# 16-Channel_PWM_Driver_PCA9685.net
KiCad netlist of a schematic drawn in EAGLE
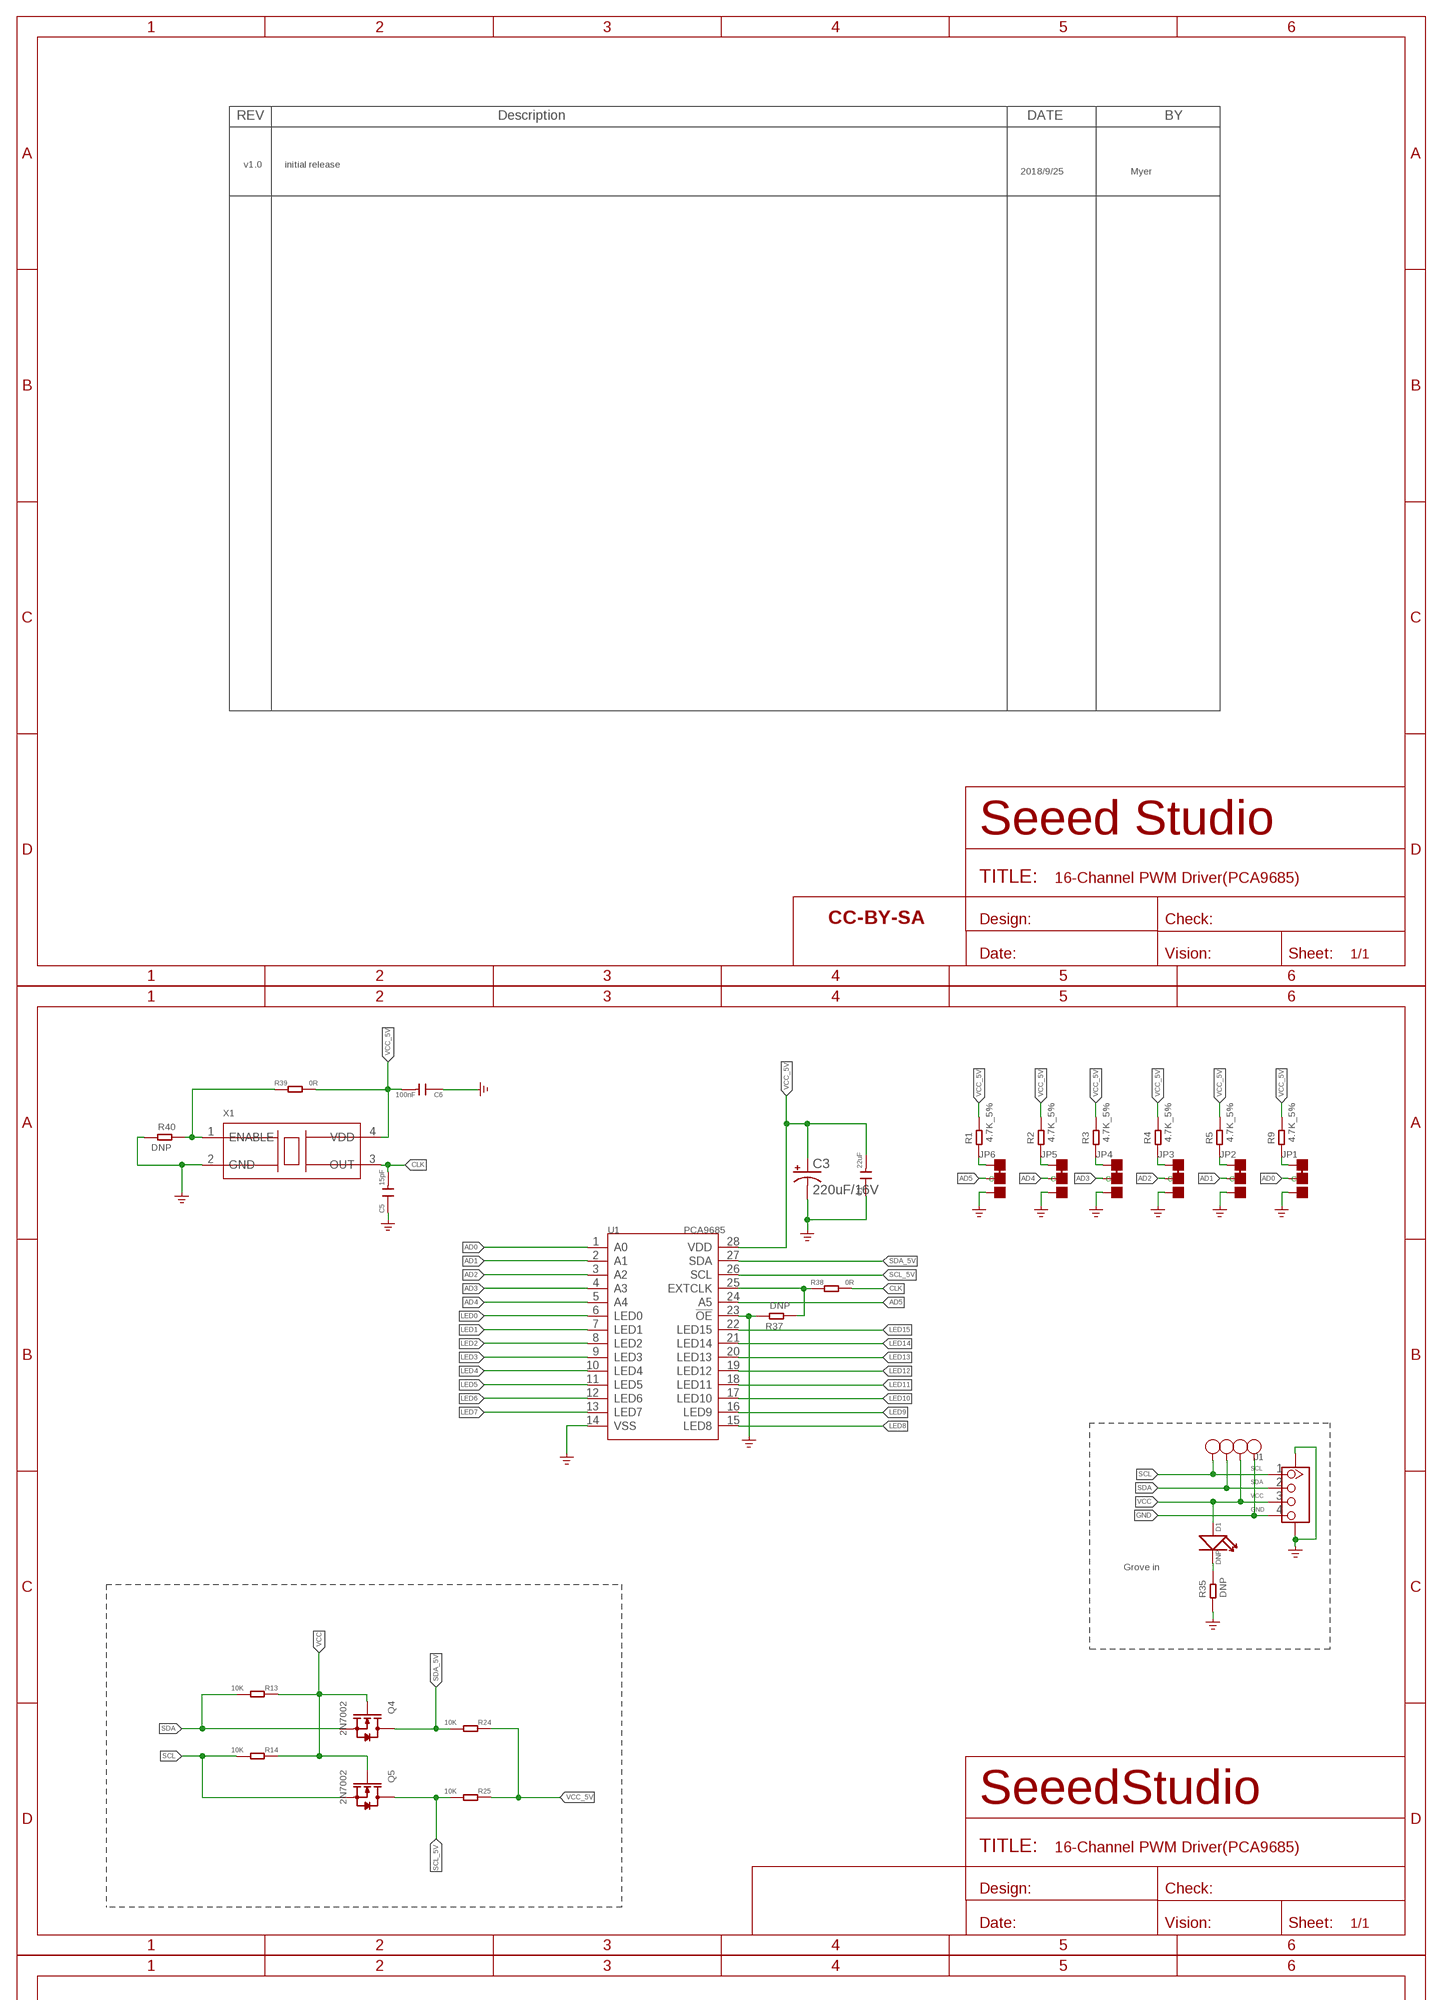
[diagram p0: schematic, sheet 1, part 1 of 2]
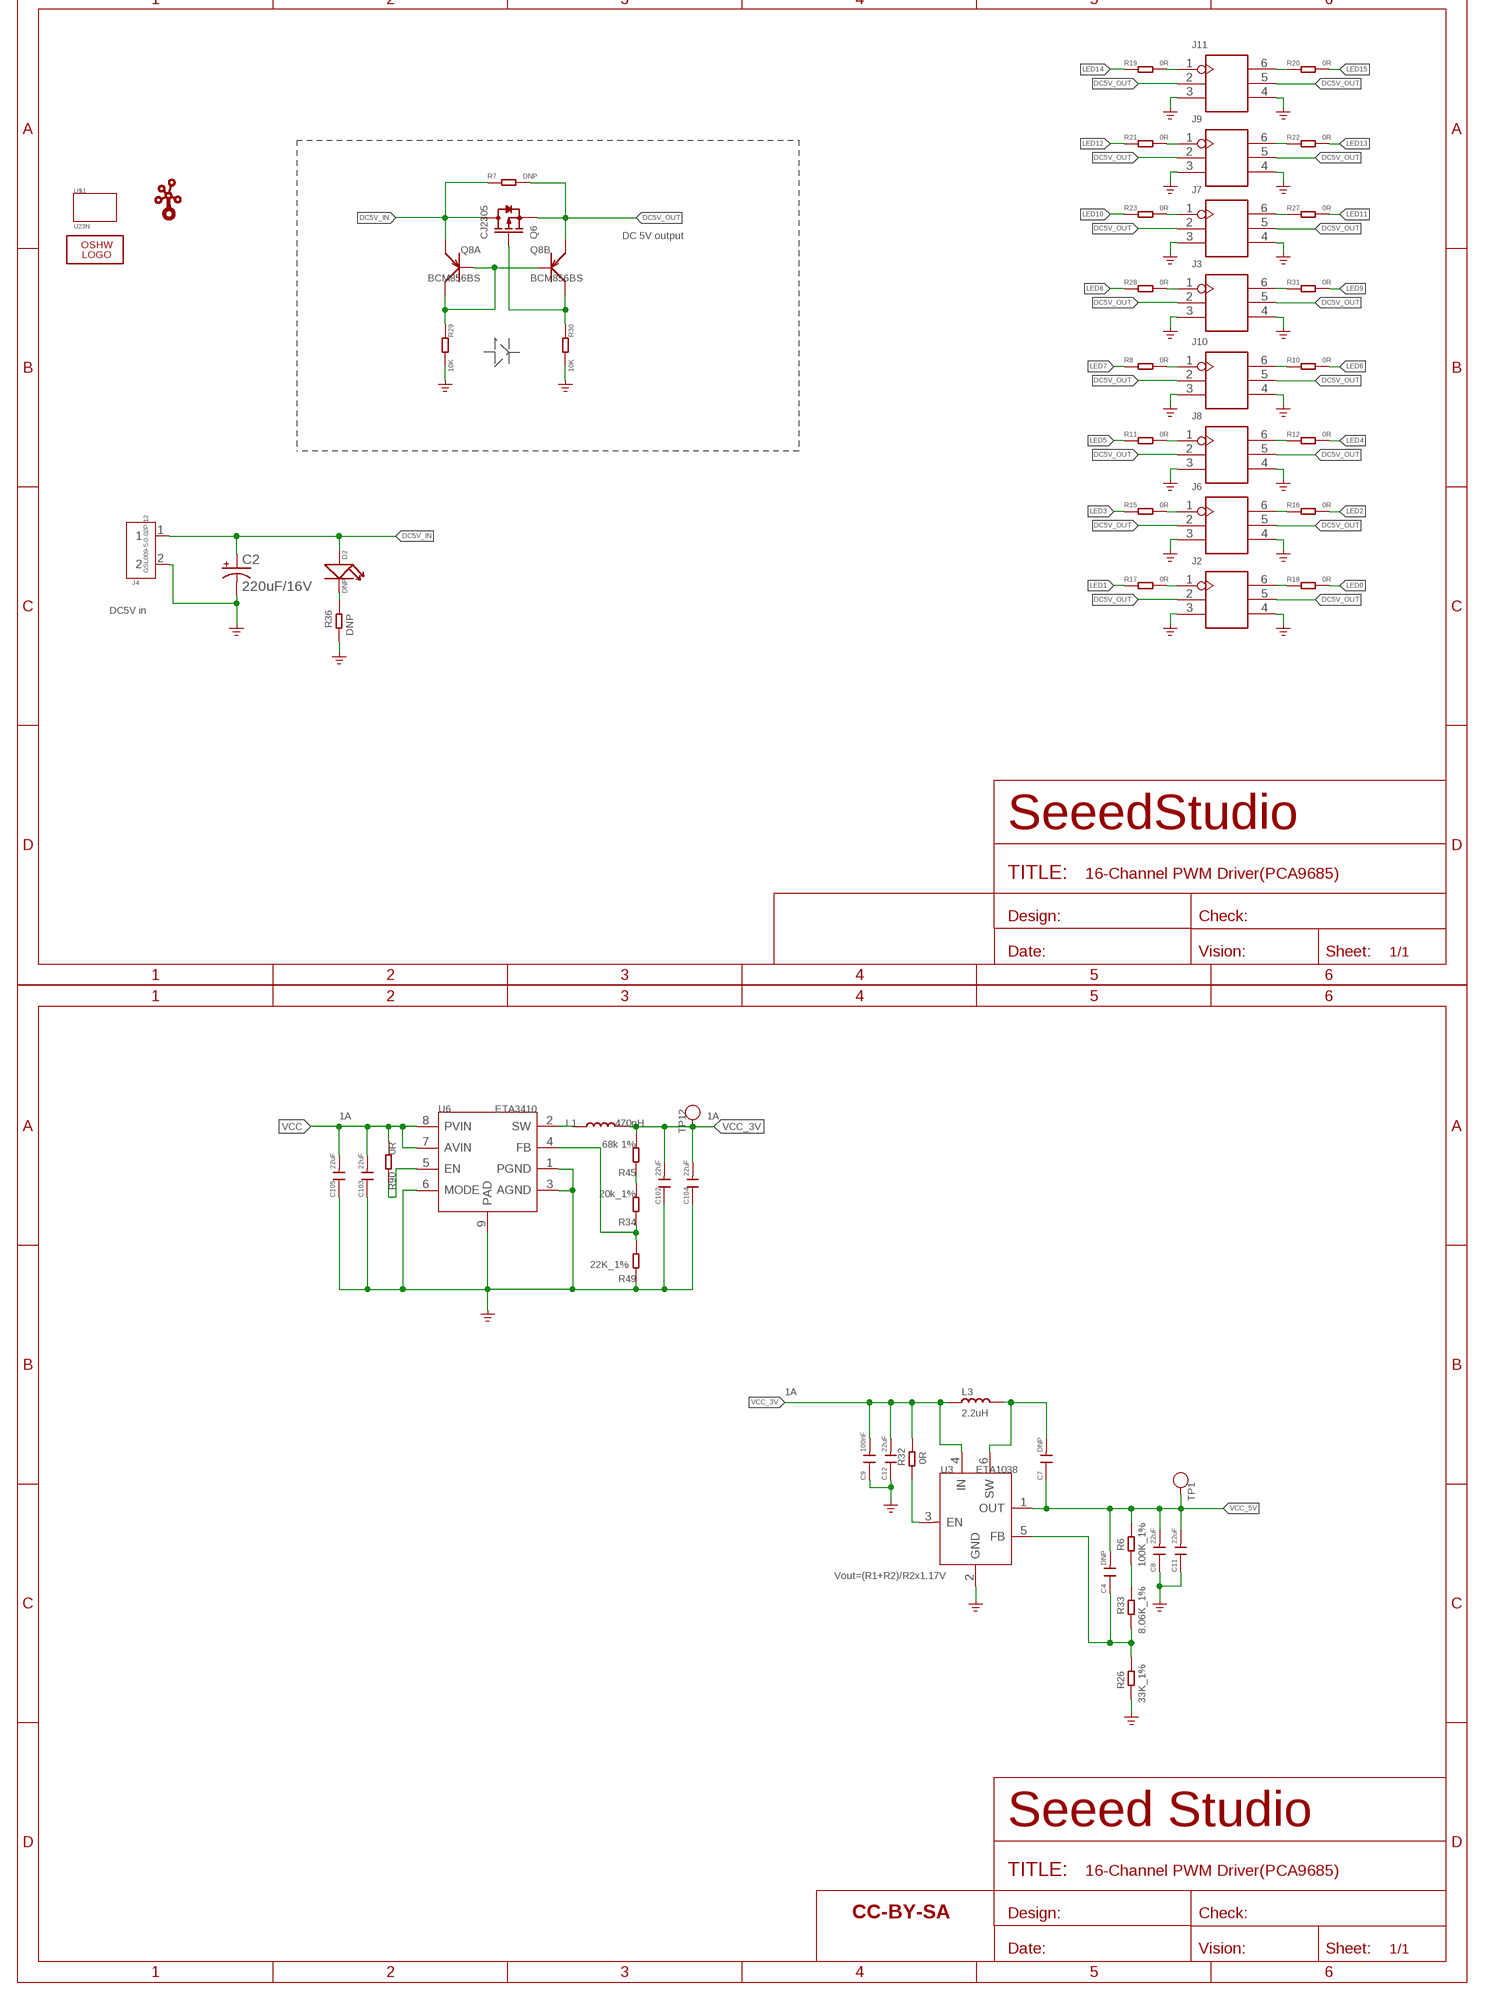
[diagram p1: schematic, sheet 1, part 2 of 2]

(export (version "E")
  (design (tool "Eeschema 10.0.6"))
  (components
    (comp (ref "C1")
      (value "22uF")
      (footprint "eagle-import:C0805")
      (libsource (lib "eagle-import") (part "C-0805"))
    )
    (comp (ref "C2")
      (value "220uF/16V")
      (footprint "eagle-import:PANASONIC_D")
      (libsource (lib "eagle-import") (part "CPOL-USD"))
    )
    (comp (ref "C3")
      (value "220uF/16V")
      (footprint "eagle-import:PANASONIC_D")
      (libsource (lib "eagle-import") (part "CPOL-USD"))
    )
    (comp (ref "C4")
      (value "DNP")
      (footprint "eagle-import:C0603")
      (libsource (lib "eagle-import") (part "C-0603"))
    )
    (comp (ref "C5")
      (value "15pF")
      (footprint "eagle-import:C0603")
      (libsource (lib "eagle-import") (part "C-0603"))
    )
    (comp (ref "C6")
      (value "100nF")
      (footprint "eagle-import:C0603")
      (libsource (lib "eagle-import") (part "C-0603"))
    )
    (comp (ref "C7")
      (value "DNP")
      (footprint "eagle-import:C0603")
      (libsource (lib "eagle-import") (part "C-0603"))
    )
    (comp (ref "C8")
      (value "22uF")
      (footprint "eagle-import:C0603")
      (libsource (lib "eagle-import") (part "C-0603"))
    )
    (comp (ref "C9")
      (value "100nF")
      (footprint "eagle-import:C0603")
      (libsource (lib "eagle-import") (part "C-0603"))
    )
    (comp (ref "C11")
      (value "22uF")
      (footprint "eagle-import:C0603")
      (libsource (lib "eagle-import") (part "C-0603"))
    )
    (comp (ref "C12")
      (value "22uF")
      (footprint "eagle-import:C0603")
      (libsource (lib "eagle-import") (part "C-0603"))
    )
    (comp (ref "C102")
      (value "22uF")
      (footprint "eagle-import:C0603")
      (libsource (lib "eagle-import") (part "C-0603"))
    )
    (comp (ref "C103")
      (value "22uF")
      (footprint "eagle-import:C0603")
      (libsource (lib "eagle-import") (part "C-0603"))
    )
    (comp (ref "C104")
      (value "22uF")
      (footprint "eagle-import:C0603")
      (libsource (lib "eagle-import") (part "C-0603"))
    )
    (comp (ref "C105")
      (value "22uF")
      (footprint "eagle-import:C0603")
      (libsource (lib "eagle-import") (part "C-0603"))
    )
    (comp (ref "D1")
      (value "DNP")
      (footprint "eagle-import:LED-0603")
      (libsource (lib "eagle-import") (part "LED'0603'"))
    )
    (comp (ref "D2")
      (value "DNP")
      (footprint "eagle-import:LED-0603")
      (libsource (lib "eagle-import") (part "LED'0603'"))
    )
    (comp (ref "FR1")
      (value "SEEEDSTUDIO-OPEN-SCH-FRAME")
      (footprint "eagle-import:SEEEDSTUDIO-PCB-FRAME")
      (libsource (lib "eagle-import") (part "SEEEDSTUDIO-OPEN-SCH-FRAME"))
    )
    (comp (ref "FR2")
      (value "SEEEDSTUDIO-OPEN-SCH-FRAME")
      (footprint "eagle-import:SEEEDSTUDIO-PCB-FRAME")
      (libsource (lib "eagle-import") (part "SEEEDSTUDIO-OPEN-SCH-FRAME"))
    )
    (comp (ref "GND1")
      (value "TEST-POINT'4545'")
      (footprint "eagle-import:TP-D45MIL")
      (fields (field (name "PARTNO") "DNP"))
      (libsource (lib "eagle-import") (part "TEST-POINT'4545'"))
    )
    (comp (ref "J1")
      (value "GROVE-CONNECTOR-SMD'90D'")
      (footprint "eagle-import:HW4-SMD-2.0-90D")
      (libsource (lib "eagle-import") (part "GROVE-CONNECTOR-SMD'90D'"))
    )
    (comp (ref "J2")
      (value "HEADER-2X3P-2.54")
      (footprint "eagle-import:H2X3-2.54")
      (libsource (lib "eagle-import") (part "HEADER-2X3P-2.54"))
    )
    (comp (ref "J3")
      (value "HEADER-2X3P-2.54")
      (footprint "eagle-import:H2X3-2.54")
      (libsource (lib "eagle-import") (part "HEADER-2X3P-2.54"))
    )
    (comp (ref "J4")
      (value "GSL009-5.0-02P-12")
      (footprint "eagle-import:2P-5.0-10.6X10X14.8H")
      (libsource (lib "eagle-import") (part "SCREW-TERMINAL-2P'5.0-10.6X10X14.8H'"))
    )
    (comp (ref "J6")
      (value "HEADER-2X3P-2.54")
      (footprint "eagle-import:H2X3-2.54")
      (libsource (lib "eagle-import") (part "HEADER-2X3P-2.54"))
    )
    (comp (ref "J7")
      (value "HEADER-2X3P-2.54")
      (footprint "eagle-import:H2X3-2.54")
      (libsource (lib "eagle-import") (part "HEADER-2X3P-2.54"))
    )
    (comp (ref "J8")
      (value "HEADER-2X3P-2.54")
      (footprint "eagle-import:H2X3-2.54")
      (libsource (lib "eagle-import") (part "HEADER-2X3P-2.54"))
    )
    (comp (ref "J9")
      (value "HEADER-2X3P-2.54")
      (footprint "eagle-import:H2X3-2.54")
      (libsource (lib "eagle-import") (part "HEADER-2X3P-2.54"))
    )
    (comp (ref "J10")
      (value "HEADER-2X3P-2.54")
      (footprint "eagle-import:H2X3-2.54")
      (libsource (lib "eagle-import") (part "HEADER-2X3P-2.54"))
    )
    (comp (ref "J11")
      (value "HEADER-2X3P-2.54")
      (footprint "eagle-import:H2X3-2.54")
      (libsource (lib "eagle-import") (part "HEADER-2X3P-2.54"))
    )
    (comp (ref "JP1")
      (value "JP-3P-SHORT")
      (footprint "eagle-import:3P-SMD-SHORT")
      (libsource (lib "eagle-import") (part "JP-3P-SHORT"))
    )
    (comp (ref "JP2")
      (value "JP-3P-SHORT")
      (footprint "eagle-import:3P-SMD-SHORT")
      (libsource (lib "eagle-import") (part "JP-3P-SHORT"))
    )
    (comp (ref "JP3")
      (value "JP-3P-SHORT")
      (footprint "eagle-import:3P-SMD-SHORT")
      (libsource (lib "eagle-import") (part "JP-3P-SHORT"))
    )
    (comp (ref "JP4")
      (value "JP-3P-SHORT")
      (footprint "eagle-import:3P-SMD-SHORT")
      (libsource (lib "eagle-import") (part "JP-3P-SHORT"))
    )
    (comp (ref "JP5")
      (value "JP-3P-SHORT")
      (footprint "eagle-import:3P-SMD-SHORT")
      (libsource (lib "eagle-import") (part "JP-3P-SHORT"))
    )
    (comp (ref "JP6")
      (value "JP-3P-SHORT")
      (footprint "eagle-import:3P-SMD-SHORT")
      (libsource (lib "eagle-import") (part "JP-3P-SHORT"))
    )
    (comp (ref "L1")
      (value "470nH")
      (footprint "eagle-import:L201610")
      (libsource (lib "eagle-import") (part "L-MPM201610SR33_T"))
    )
    (comp (ref "L3")
      (value "2.2uH")
      (footprint "eagle-import:L0806")
      (libsource (lib "eagle-import") (part "INDUCTOR/FERRITE-BEAD'0806'"))
    )
    (comp (ref "LOGO2")
      (value "LOGO-OSHW-FILLX0200-NT")
      (footprint "eagle-import:OSHW_FILLX200_NOTEXT")
      (fields (field (name "PARTNO") "DNP"))
      (libsource (lib "eagle-import") (part "LOGO-OSHW-FILLX0200-NT"))
    )
    (comp (ref "Q4")
      (value "2N7002")
      (footprint "eagle-import:SOT-323")
      (libsource (lib "eagle-import") (part "MOSFET-N+'SI1304BDL'"))
    )
    (comp (ref "Q5")
      (value "2N7002")
      (footprint "eagle-import:SOT-323")
      (libsource (lib "eagle-import") (part "MOSFET-N+'SI1304BDL'"))
    )
    (comp (ref "Q6")
      (value "CJ2305")
      (footprint "eagle-import:SOT-23")
      (libsource (lib "eagle-import") (part "MOSFET-P'SI2323CDS/SI2305DS{lt}BR{gt}'"))
    )
    (comp (ref "Q8")
      (value "BCM856BS")
      (footprint "eagle-import:SOT-363")
      (libsource (lib "eagle-import") (part "TRANSISTOR-DUAL-PNP"))
    )
    (comp (ref "R1")
      (value "4.7K_5%")
      (footprint "eagle-import:R0603")
      (libsource (lib "eagle-import") (part "R-0603"))
    )
    (comp (ref "R2")
      (value "4.7K_5%")
      (footprint "eagle-import:R0603")
      (libsource (lib "eagle-import") (part "R-0603"))
    )
    (comp (ref "R3")
      (value "4.7K_5%")
      (footprint "eagle-import:R0603")
      (libsource (lib "eagle-import") (part "R-0603"))
    )
    (comp (ref "R4")
      (value "4.7K_5%")
      (footprint "eagle-import:R0603")
      (libsource (lib "eagle-import") (part "R-0603"))
    )
    (comp (ref "R5")
      (value "4.7K_5%")
      (footprint "eagle-import:R0603")
      (libsource (lib "eagle-import") (part "R-0603"))
    )
    (comp (ref "R6")
      (value "100K_1%")
      (footprint "eagle-import:R0603")
      (libsource (lib "eagle-import") (part "R-0603"))
    )
    (comp (ref "R7")
      (value "DNP")
      (footprint "eagle-import:R0805")
      (libsource (lib "eagle-import") (part "R-0805"))
    )
    (comp (ref "R8")
      (value "0R")
      (footprint "eagle-import:R0603")
      (libsource (lib "eagle-import") (part "R-0603"))
    )
    (comp (ref "R9")
      (value "4.7K_5%")
      (footprint "eagle-import:R0603")
      (libsource (lib "eagle-import") (part "R-0603"))
    )
    (comp (ref "R10")
      (value "0R")
      (footprint "eagle-import:R0603")
      (libsource (lib "eagle-import") (part "R-0603"))
    )
    (comp (ref "R11")
      (value "0R")
      (footprint "eagle-import:R0603")
      (libsource (lib "eagle-import") (part "R-0603"))
    )
    (comp (ref "R12")
      (value "0R")
      (footprint "eagle-import:R0603")
      (libsource (lib "eagle-import") (part "R-0603"))
    )
    (comp (ref "R13")
      (value "10K")
      (footprint "eagle-import:R0603")
      (libsource (lib "eagle-import") (part "R-0603"))
    )
    (comp (ref "R14")
      (value "10K")
      (footprint "eagle-import:R0603")
      (libsource (lib "eagle-import") (part "R-0603"))
    )
    (comp (ref "R15")
      (value "0R")
      (footprint "eagle-import:R0603")
      (libsource (lib "eagle-import") (part "R-0603"))
    )
    (comp (ref "R16")
      (value "0R")
      (footprint "eagle-import:R0603")
      (libsource (lib "eagle-import") (part "R-0603"))
    )
    (comp (ref "R17")
      (value "0R")
      (footprint "eagle-import:R0603")
      (libsource (lib "eagle-import") (part "R-0603"))
    )
    (comp (ref "R18")
      (value "0R")
      (footprint "eagle-import:R0603")
      (libsource (lib "eagle-import") (part "R-0603"))
    )
    (comp (ref "R19")
      (value "0R")
      (footprint "eagle-import:R0603")
      (libsource (lib "eagle-import") (part "R-0603"))
    )
    (comp (ref "R20")
      (value "0R")
      (footprint "eagle-import:R0603")
      (libsource (lib "eagle-import") (part "R-0603"))
    )
    (comp (ref "R21")
      (value "0R")
      (footprint "eagle-import:R0603")
      (libsource (lib "eagle-import") (part "R-0603"))
    )
    (comp (ref "R22")
      (value "0R")
      (footprint "eagle-import:R0603")
      (libsource (lib "eagle-import") (part "R-0603"))
    )
    (comp (ref "R23")
      (value "0R")
      (footprint "eagle-import:R0603")
      (libsource (lib "eagle-import") (part "R-0603"))
    )
    (comp (ref "R24")
      (value "10K")
      (footprint "eagle-import:R0603")
      (libsource (lib "eagle-import") (part "R-0603"))
    )
    (comp (ref "R25")
      (value "10K")
      (footprint "eagle-import:R0603")
      (libsource (lib "eagle-import") (part "R-0603"))
    )
    (comp (ref "R26")
      (value "33K_1%")
      (footprint "eagle-import:R0603")
      (libsource (lib "eagle-import") (part "R-0603"))
    )
    (comp (ref "R27")
      (value "0R")
      (footprint "eagle-import:R0603")
      (libsource (lib "eagle-import") (part "R-0603"))
    )
    (comp (ref "R28")
      (value "0R")
      (footprint "eagle-import:R0603")
      (libsource (lib "eagle-import") (part "R-0603"))
    )
    (comp (ref "R29")
      (value "10K")
      (footprint "eagle-import:R0603")
      (libsource (lib "eagle-import") (part "R-0603"))
    )
    (comp (ref "R30")
      (value "10K")
      (footprint "eagle-import:R0603")
      (libsource (lib "eagle-import") (part "R-0603"))
    )
    (comp (ref "R31")
      (value "0R")
      (footprint "eagle-import:R0603")
      (libsource (lib "eagle-import") (part "R-0603"))
    )
    (comp (ref "R32")
      (value "0R")
      (footprint "eagle-import:R0603")
      (libsource (lib "eagle-import") (part "R-0603"))
    )
    (comp (ref "R33")
      (value "8.06K_1%")
      (footprint "eagle-import:R0603")
      (libsource (lib "eagle-import") (part "R-0603"))
    )
    (comp (ref "R34")
      (value "20k_1%")
      (footprint "eagle-import:R0603")
      (libsource (lib "eagle-import") (part "R-0603"))
    )
    (comp (ref "R35")
      (value "DNP")
      (footprint "eagle-import:R0603")
      (libsource (lib "eagle-import") (part "R-0603"))
    )
    (comp (ref "R36")
      (value "DNP")
      (footprint "eagle-import:R0603")
      (libsource (lib "eagle-import") (part "R-0603"))
    )
    (comp (ref "R37")
      (value "DNP")
      (footprint "eagle-import:R0603")
      (libsource (lib "eagle-import") (part "R-0603"))
    )
    (comp (ref "R38")
      (value "0R")
      (footprint "eagle-import:R0603")
      (libsource (lib "eagle-import") (part "R-0603"))
    )
    (comp (ref "R39")
      (value "0R")
      (footprint "eagle-import:R0603")
      (libsource (lib "eagle-import") (part "R-0603"))
    )
    (comp (ref "R40")
      (value "DNP")
      (footprint "eagle-import:R0603")
      (libsource (lib "eagle-import") (part "R-0603"))
    )
    (comp (ref "R45")
      (value "68k 1%")
      (footprint "eagle-import:R0603")
      (libsource (lib "eagle-import") (part "R-0603"))
    )
    (comp (ref "R49")
      (value "22K_1%")
      (footprint "eagle-import:R0603")
      (libsource (lib "eagle-import") (part "R-0603"))
    )
    (comp (ref "R90")
      (value "0R")
      (footprint "eagle-import:R0603")
      (libsource (lib "eagle-import") (part "R-0603"))
    )
    (comp (ref "SCL1")
      (value "TEST-POINT'4545'")
      (footprint "eagle-import:TP-D45MIL")
      (fields (field (name "PARTNO") "DNP"))
      (libsource (lib "eagle-import") (part "TEST-POINT'4545'"))
    )
    (comp (ref "SDA1")
      (value "TEST-POINT'4545'")
      (footprint "eagle-import:TP-D45MIL")
      (fields (field (name "PARTNO") "DNP"))
      (libsource (lib "eagle-import") (part "TEST-POINT'4545'"))
    )
    (comp (ref "TP1")
      (value "TEST-POINT'4545'")
      (footprint "eagle-import:TP-D45MIL")
      (fields (field (name "PARTNO") "DNP"))
      (libsource (lib "eagle-import") (part "TEST-POINT'4545'"))
    )
    (comp (ref "TP12")
      (value "TEST-POINT'4545'")
      (footprint "eagle-import:TP-D45MIL")
      (fields (field (name "PARTNO") "DNP"))
      (libsource (lib "eagle-import") (part "TEST-POINT'4545'"))
    )
    (comp (ref "U$1")
      (value "U23N")
      (footprint "eagle-import:U2_3N")
      (libsource (lib "eagle-import") (part "U23N"))
    )
    (comp (ref "U$3")
      (value "TWIGLOGOTWIGLOGO_SMALL")
      (footprint "eagle-import:TWIGLOGO_SMALL")
      (libsource (lib "eagle-import") (part "TWIGLOGOTWIGLOGO_SMALL"))
    )
    (comp (ref "U1")
      (value "PCA9685")
      (footprint "eagle-import:TSSOP28-0.65-9.7X4.4X1.2MM")
      (libsource (lib "eagle-import") (part "LED-RGB-24P-PCA9685"))
    )
    (comp (ref "U3")
      (value "ETA1038")
      (footprint "eagle-import:SOT-23-6")
      (libsource (lib "eagle-import") (part "CONVERTER-ETA1038"))
    )
    (comp (ref "U6")
      (value "ETA3410")
      (footprint "eagle-import:DFN8G-0.5-2X2MM")
      (libsource (lib "eagle-import") (part "CONVERTER-ETA3410"))
    )
    (comp (ref "VCC2")
      (value "TEST-POINT'4545'")
      (footprint "eagle-import:TP-D45MIL")
      (fields (field (name "PARTNO") "DNP"))
      (libsource (lib "eagle-import") (part "TEST-POINT'4545'"))
    )
    (comp (ref "X1")
      (value "CRYSTAL-OSCILLATOR'7050'")
      (footprint "eagle-import:OSC4-SMD-7.0X5.0X1.0MM")
      (libsource (lib "eagle-import") (part "CRYSTAL-OSCILLATOR'7050'"))
    )
  )
  (nets
    (net (code "1") (name "AD0") (class "Default")
      (node (ref "JP1") (pin "MM") (pinfunction "C_MM") (pintype "bidirectional"))
      (node (ref "U1") (pin "1") (pinfunction "A0_1") (pintype "bidirectional"))
    )
    (net (code "2") (name "AD1") (class "Default")
      (node (ref "JP2") (pin "MM") (pinfunction "C_MM") (pintype "bidirectional"))
      (node (ref "U1") (pin "2") (pinfunction "A1_2") (pintype "bidirectional"))
    )
    (net (code "3") (name "AD2") (class "Default")
      (node (ref "JP3") (pin "MM") (pinfunction "C_MM") (pintype "bidirectional"))
      (node (ref "U1") (pin "3") (pinfunction "A2_3") (pintype "bidirectional"))
    )
    (net (code "4") (name "AD3") (class "Default")
      (node (ref "JP4") (pin "MM") (pinfunction "C_MM") (pintype "bidirectional"))
      (node (ref "U1") (pin "4") (pinfunction "A3_4") (pintype "bidirectional"))
    )
    (net (code "5") (name "AD4") (class "Default")
      (node (ref "JP5") (pin "MM") (pinfunction "C_MM") (pintype "bidirectional"))
      (node (ref "U1") (pin "5") (pinfunction "A4_5") (pintype "bidirectional"))
    )
    (net (code "6") (name "AD5") (class "Default")
      (node (ref "JP6") (pin "MM") (pinfunction "C_MM") (pintype "bidirectional"))
      (node (ref "U1") (pin "24") (pinfunction "A5_24") (pintype "bidirectional"))
    )
    (net (code "7") (name "CLK") (class "Default")
      (node (ref "C5") (pin "2") (pinfunction "2_2") (pintype "passive"))
      (node (ref "R38") (pin "2") (pinfunction "2_2") (pintype "passive"))
      (node (ref "X1") (pin "3") (pinfunction "OUT_3") (pintype "bidirectional"))
    )
    (net (code "8") (name "DC5V_IN") (class "Default")
      (node (ref "C2") (pin "+") (pinfunction "+_+") (pintype "passive"))
      (node (ref "D2") (pin "+") (pinfunction "+_+") (pintype "passive"))
      (node (ref "J4") (pin "1") (pinfunction "1_1") (pintype "bidirectional"))
      (node (ref "Q6") (pin "3") (pinfunction "D_3") (pintype "passive"))
      (node (ref "Q8") (pin "1") (pinfunction "E_1") (pintype "passive"))
      (node (ref "R7") (pin "1") (pinfunction "1_1") (pintype "passive"))
    )
    (net (code "9") (name "DC5V_OUT") (class "Default")
      (node (ref "J10") (pin "2") (pinfunction "2_2") (pintype "bidirectional"))
      (node (ref "J10") (pin "5") (pinfunction "5_5") (pintype "bidirectional"))
      (node (ref "J11") (pin "2") (pinfunction "2_2") (pintype "bidirectional"))
      (node (ref "J11") (pin "5") (pinfunction "5_5") (pintype "bidirectional"))
      (node (ref "J2") (pin "2") (pinfunction "2_2") (pintype "bidirectional"))
      (node (ref "J2") (pin "5") (pinfunction "5_5") (pintype "bidirectional"))
      (node (ref "J3") (pin "2") (pinfunction "2_2") (pintype "bidirectional"))
      (node (ref "J3") (pin "5") (pinfunction "5_5") (pintype "bidirectional"))
      (node (ref "J6") (pin "2") (pinfunction "2_2") (pintype "bidirectional"))
      (node (ref "J6") (pin "5") (pinfunction "5_5") (pintype "bidirectional"))
      (node (ref "J7") (pin "2") (pinfunction "2_2") (pintype "bidirectional"))
      (node (ref "J7") (pin "5") (pinfunction "5_5") (pintype "bidirectional"))
      (node (ref "J8") (pin "2") (pinfunction "2_2") (pintype "bidirectional"))
      (node (ref "J8") (pin "5") (pinfunction "5_5") (pintype "bidirectional"))
      (node (ref "J9") (pin "2") (pinfunction "2_2") (pintype "bidirectional"))
      (node (ref "J9") (pin "5") (pinfunction "5_5") (pintype "bidirectional"))
      (node (ref "Q6") (pin "2") (pinfunction "S_2") (pintype "passive"))
      (node (ref "Q8") (pin "4") (pinfunction "E_4") (pintype "passive"))
      (node (ref "R7") (pin "2") (pinfunction "2_2") (pintype "passive"))
    )
    (net (code "10") (name "GND") (class "Default")
      (node (ref "C1") (pin "1") (pinfunction "1_1") (pintype "passive"))
      (node (ref "C102") (pin "1") (pinfunction "1_1") (pintype "passive"))
      (node (ref "C103") (pin "1") (pinfunction "1_1") (pintype "passive"))
      (node (ref "C104") (pin "1") (pinfunction "1_1") (pintype "passive"))
      (node (ref "C105") (pin "1") (pinfunction "1_1") (pintype "passive"))
      (node (ref "C11") (pin "1") (pinfunction "1_1") (pintype "passive"))
      (node (ref "C12") (pin "1") (pinfunction "1_1") (pintype "passive"))
      (node (ref "C2") (pin "-") (pinfunction "-_-") (pintype "passive"))
      (node (ref "C3") (pin "-") (pinfunction "-_-") (pintype "passive"))
      (node (ref "C5") (pin "1") (pinfunction "1_1") (pintype "passive"))
      (node (ref "C6") (pin "1") (pinfunction "1_1") (pintype "passive"))
      (node (ref "C8") (pin "1") (pinfunction "1_1") (pintype "passive"))
      (node (ref "C9") (pin "1") (pinfunction "1_1") (pintype "passive"))
      (node (ref "J1") (pin "4") (pinfunction "4_4") (pintype "bidirectional"))
      (node (ref "J1") (pin "SS1") (pinfunction "SS1_SS1") (pintype "bidirectional"))
      (node (ref "J1") (pin "SS2") (pinfunction "SS2_SS2") (pintype "bidirectional"))
      (node (ref "J10") (pin "3") (pinfunction "3_3") (pintype "bidirectional"))
      (node (ref "J10") (pin "4") (pinfunction "4_4") (pintype "bidirectional"))
      (node (ref "J11") (pin "3") (pinfunction "3_3") (pintype "bidirectional"))
      (node (ref "J11") (pin "4") (pinfunction "4_4") (pintype "bidirectional"))
      (node (ref "J2") (pin "3") (pinfunction "3_3") (pintype "bidirectional"))
      (node (ref "J2") (pin "4") (pinfunction "4_4") (pintype "bidirectional"))
      (node (ref "J3") (pin "3") (pinfunction "3_3") (pintype "bidirectional"))
      (node (ref "J3") (pin "4") (pinfunction "4_4") (pintype "bidirectional"))
      (node (ref "J4") (pin "2") (pinfunction "2_2") (pintype "bidirectional"))
      (node (ref "J6") (pin "3") (pinfunction "3_3") (pintype "bidirectional"))
      (node (ref "J6") (pin "4") (pinfunction "4_4") (pintype "bidirectional"))
      (node (ref "J7") (pin "3") (pinfunction "3_3") (pintype "bidirectional"))
      (node (ref "J7") (pin "4") (pinfunction "4_4") (pintype "bidirectional"))
      (node (ref "J8") (pin "3") (pinfunction "3_3") (pintype "bidirectional"))
      (node (ref "J8") (pin "4") (pinfunction "4_4") (pintype "bidirectional"))
      (node (ref "J9") (pin "3") (pinfunction "3_3") (pintype "bidirectional"))
      (node (ref "J9") (pin "4") (pinfunction "4_4") (pintype "bidirectional"))
      (node (ref "JP1") (pin "00") (pinfunction "R_00") (pintype "bidirectional"))
      (node (ref "JP2") (pin "00") (pinfunction "R_00") (pintype "bidirectional"))
      (node (ref "JP3") (pin "00") (pinfunction "R_00") (pintype "bidirectional"))
      (node (ref "JP4") (pin "00") (pinfunction "R_00") (pintype "bidirectional"))
      (node (ref "JP5") (pin "00") (pinfunction "R_00") (pintype "bidirectional"))
      (node (ref "JP6") (pin "00") (pinfunction "R_00") (pintype "bidirectional"))
      (node (ref "R26") (pin "1") (pinfunction "1_1") (pintype "passive"))
      (node (ref "R29") (pin "2") (pinfunction "2_2") (pintype "passive"))
      (node (ref "R30") (pin "2") (pinfunction "2_2") (pintype "passive"))
      (node (ref "R35") (pin "2") (pinfunction "2_2") (pintype "passive"))
      (node (ref "R36") (pin "2") (pinfunction "2_2") (pintype "passive"))
      (node (ref "R37") (pin "1") (pinfunction "1_1") (pintype "passive"))
      (node (ref "R40") (pin "2") (pinfunction "2_2") (pintype "passive"))
      (node (ref "R49") (pin "1") (pinfunction "1_1") (pintype "passive"))
      (node (ref "SCL1") (pin "T") (pinfunction "T_T") (pintype "bidirectional"))
      (node (ref "U1") (pin "14") (pinfunction "VSS_14") (pintype "bidirectional"))
      (node (ref "U1") (pin "23") (pinfunction "~{OE}_23") (pintype "bidirectional"))
      (node (ref "U3") (pin "2") (pinfunction "GND_2") (pintype "bidirectional"))
      (node (ref "U6") (pin "1") (pinfunction "PGND_1") (pintype "bidirectional"))
      (node (ref "U6") (pin "3") (pinfunction "AGND_3") (pintype "bidirectional"))
      (node (ref "U6") (pin "6") (pinfunction "MODE_6") (pintype "bidirectional"))
      (node (ref "U6") (pin "9") (pinfunction "PAD_9") (pintype "bidirectional"))
      (node (ref "X1") (pin "2") (pinfunction "GND_2") (pintype "bidirectional"))
    )
    (net (code "11") (name "LED0") (class "Default")
      (node (ref "R18") (pin "2") (pinfunction "2_2") (pintype "passive"))
      (node (ref "U1") (pin "6") (pinfunction "LED0_6") (pintype "bidirectional"))
    )
    (net (code "12") (name "LED1") (class "Default")
      (node (ref "R17") (pin "1") (pinfunction "1_1") (pintype "passive"))
      (node (ref "U1") (pin "7") (pinfunction "LED1_7") (pintype "bidirectional"))
    )
    (net (code "13") (name "LED2") (class "Default")
      (node (ref "R16") (pin "2") (pinfunction "2_2") (pintype "passive"))
      (node (ref "U1") (pin "8") (pinfunction "LED2_8") (pintype "bidirectional"))
    )
    (net (code "14") (name "LED3") (class "Default")
      (node (ref "R15") (pin "1") (pinfunction "1_1") (pintype "passive"))
      (node (ref "U1") (pin "9") (pinfunction "LED3_9") (pintype "bidirectional"))
    )
    (net (code "15") (name "LED4") (class "Default")
      (node (ref "R12") (pin "2") (pinfunction "2_2") (pintype "passive"))
      (node (ref "U1") (pin "10") (pinfunction "LED4_10") (pintype "bidirectional"))
    )
    (net (code "16") (name "LED5") (class "Default")
      (node (ref "R11") (pin "1") (pinfunction "1_1") (pintype "passive"))
      (node (ref "U1") (pin "11") (pinfunction "LED5_11") (pintype "bidirectional"))
    )
    (net (code "17") (name "LED6") (class "Default")
      (node (ref "R10") (pin "2") (pinfunction "2_2") (pintype "passive"))
      (node (ref "U1") (pin "12") (pinfunction "LED6_12") (pintype "bidirectional"))
    )
    (net (code "18") (name "LED7") (class "Default")
      (node (ref "R8") (pin "1") (pinfunction "1_1") (pintype "passive"))
      (node (ref "U1") (pin "13") (pinfunction "LED7_13") (pintype "bidirectional"))
    )
    (net (code "19") (name "LED8") (class "Default")
      (node (ref "R28") (pin "1") (pinfunction "1_1") (pintype "passive"))
      (node (ref "U1") (pin "15") (pinfunction "LED8_15") (pintype "bidirectional"))
    )
    (net (code "20") (name "LED9") (class "Default")
      (node (ref "R31") (pin "2") (pinfunction "2_2") (pintype "passive"))
      (node (ref "U1") (pin "16") (pinfunction "LED9_16") (pintype "bidirectional"))
    )
    (net (code "21") (name "LED10") (class "Default")
      (node (ref "R23") (pin "1") (pinfunction "1_1") (pintype "passive"))
      (node (ref "U1") (pin "17") (pinfunction "LED10_17") (pintype "bidirectional"))
    )
    (net (code "22") (name "LED11") (class "Default")
      (node (ref "R27") (pin "2") (pinfunction "2_2") (pintype "passive"))
      (node (ref "U1") (pin "18") (pinfunction "LED11_18") (pintype "bidirectional"))
    )
    (net (code "23") (name "LED12") (class "Default")
      (node (ref "R21") (pin "1") (pinfunction "1_1") (pintype "passive"))
      (node (ref "U1") (pin "19") (pinfunction "LED12_19") (pintype "bidirectional"))
    )
    (net (code "24") (name "LED13") (class "Default")
      (node (ref "R22") (pin "2") (pinfunction "2_2") (pintype "passive"))
      (node (ref "U1") (pin "20") (pinfunction "LED13_20") (pintype "bidirectional"))
    )
    (net (code "25") (name "LED14") (class "Default")
      (node (ref "R19") (pin "1") (pinfunction "1_1") (pintype "passive"))
      (node (ref "U1") (pin "21") (pinfunction "LED14_21") (pintype "bidirectional"))
    )
    (net (code "26") (name "LED15") (class "Default")
      (node (ref "R20") (pin "2") (pinfunction "2_2") (pintype "passive"))
      (node (ref "U1") (pin "22") (pinfunction "LED15_22") (pintype "bidirectional"))
    )
    (net (code "27") (name "Net-(D1-Pad-)") (class "Default")
      (node (ref "D1") (pin "-") (pinfunction "-_-") (pintype "passive"))
      (node (ref "R35") (pin "1") (pinfunction "1_1") (pintype "passive"))
    )
    (net (code "28") (name "Net-(D2-Pad-)") (class "Default")
      (node (ref "D2") (pin "-") (pinfunction "-_-") (pintype "passive"))
      (node (ref "R36") (pin "1") (pinfunction "1_1") (pintype "passive"))
    )
    (net (code "29") (name "Net-(J2-Pad1)") (class "Default")
      (node (ref "J2") (pin "1") (pinfunction "1_1") (pintype "bidirectional"))
      (node (ref "R17") (pin "2") (pinfunction "2_2") (pintype "passive"))
    )
    (net (code "30") (name "Net-(J2-Pad6)") (class "Default")
      (node (ref "J2") (pin "6") (pinfunction "6_6") (pintype "bidirectional"))
      (node (ref "R18") (pin "1") (pinfunction "1_1") (pintype "passive"))
    )
    (net (code "31") (name "Net-(J3-Pad1)") (class "Default")
      (node (ref "J3") (pin "1") (pinfunction "1_1") (pintype "bidirectional"))
      (node (ref "R28") (pin "2") (pinfunction "2_2") (pintype "passive"))
    )
    (net (code "32") (name "Net-(J3-Pad6)") (class "Default")
      (node (ref "J3") (pin "6") (pinfunction "6_6") (pintype "bidirectional"))
      (node (ref "R31") (pin "1") (pinfunction "1_1") (pintype "passive"))
    )
    (net (code "33") (name "Net-(J6-Pad1)") (class "Default")
      (node (ref "J6") (pin "1") (pinfunction "1_1") (pintype "bidirectional"))
      (node (ref "R15") (pin "2") (pinfunction "2_2") (pintype "passive"))
    )
    (net (code "34") (name "Net-(J6-Pad6)") (class "Default")
      (node (ref "J6") (pin "6") (pinfunction "6_6") (pintype "bidirectional"))
      (node (ref "R16") (pin "1") (pinfunction "1_1") (pintype "passive"))
    )
    (net (code "35") (name "Net-(J7-Pad1)") (class "Default")
      (node (ref "J7") (pin "1") (pinfunction "1_1") (pintype "bidirectional"))
      (node (ref "R23") (pin "2") (pinfunction "2_2") (pintype "passive"))
    )
    (net (code "36") (name "Net-(J7-Pad6)") (class "Default")
      (node (ref "J7") (pin "6") (pinfunction "6_6") (pintype "bidirectional"))
      (node (ref "R27") (pin "1") (pinfunction "1_1") (pintype "passive"))
    )
    (net (code "37") (name "Net-(J8-Pad1)") (class "Default")
      (node (ref "J8") (pin "1") (pinfunction "1_1") (pintype "bidirectional"))
      (node (ref "R11") (pin "2") (pinfunction "2_2") (pintype "passive"))
    )
    (net (code "38") (name "Net-(J8-Pad6)") (class "Default")
      (node (ref "J8") (pin "6") (pinfunction "6_6") (pintype "bidirectional"))
      (node (ref "R12") (pin "1") (pinfunction "1_1") (pintype "passive"))
    )
    (net (code "39") (name "Net-(J9-Pad1)") (class "Default")
      (node (ref "J9") (pin "1") (pinfunction "1_1") (pintype "bidirectional"))
      (node (ref "R21") (pin "2") (pinfunction "2_2") (pintype "passive"))
    )
    (net (code "40") (name "Net-(J9-Pad6)") (class "Default")
      (node (ref "J9") (pin "6") (pinfunction "6_6") (pintype "bidirectional"))
      (node (ref "R22") (pin "1") (pinfunction "1_1") (pintype "passive"))
    )
    (net (code "41") (name "Net-(J10-Pad1)") (class "Default")
      (node (ref "J10") (pin "1") (pinfunction "1_1") (pintype "bidirectional"))
      (node (ref "R8") (pin "2") (pinfunction "2_2") (pintype "passive"))
    )
    (net (code "42") (name "Net-(J10-Pad6)") (class "Default")
      (node (ref "J10") (pin "6") (pinfunction "6_6") (pintype "bidirectional"))
      (node (ref "R10") (pin "1") (pinfunction "1_1") (pintype "passive"))
    )
    (net (code "43") (name "Net-(J11-Pad1)") (class "Default")
      (node (ref "J11") (pin "1") (pinfunction "1_1") (pintype "bidirectional"))
      (node (ref "R19") (pin "2") (pinfunction "2_2") (pintype "passive"))
    )
    (net (code "44") (name "Net-(J11-Pad6)") (class "Default")
      (node (ref "J11") (pin "6") (pinfunction "6_6") (pintype "bidirectional"))
      (node (ref "R20") (pin "1") (pinfunction "1_1") (pintype "passive"))
    )
    (net (code "45") (name "Net-(JP1-L)") (class "Default")
      (node (ref "JP1") (pin "11") (pinfunction "L_11") (pintype "bidirectional"))
      (node (ref "R9") (pin "2") (pinfunction "2_2") (pintype "passive"))
    )
    (net (code "46") (name "Net-(JP2-L)") (class "Default")
      (node (ref "JP2") (pin "11") (pinfunction "L_11") (pintype "bidirectional"))
      (node (ref "R5") (pin "2") (pinfunction "2_2") (pintype "passive"))
    )
    (net (code "47") (name "Net-(JP3-L)") (class "Default")
      (node (ref "JP3") (pin "11") (pinfunction "L_11") (pintype "bidirectional"))
      (node (ref "R4") (pin "2") (pinfunction "2_2") (pintype "passive"))
    )
    (net (code "48") (name "Net-(JP4-L)") (class "Default")
      (node (ref "JP4") (pin "11") (pinfunction "L_11") (pintype "bidirectional"))
      (node (ref "R3") (pin "2") (pinfunction "2_2") (pintype "passive"))
    )
    (net (code "49") (name "Net-(JP5-L)") (class "Default")
      (node (ref "JP5") (pin "11") (pinfunction "L_11") (pintype "bidirectional"))
      (node (ref "R2") (pin "2") (pinfunction "2_2") (pintype "passive"))
    )
    (net (code "50") (name "Net-(JP6-L)") (class "Default")
      (node (ref "JP6") (pin "11") (pinfunction "L_11") (pintype "bidirectional"))
      (node (ref "R1") (pin "2") (pinfunction "2_2") (pintype "passive"))
    )
    (net (code "51") (name "Net-(Q6-G)") (class "Default")
      (node (ref "Q6") (pin "1") (pinfunction "G_1") (pintype "passive"))
      (node (ref "Q8") (pin "3") (pinfunction "C_3") (pintype "passive"))
      (node (ref "R30") (pin "1") (pinfunction "1_1") (pintype "passive"))
    )
    (net (code "52") (name "Net-(Q8A-B)") (class "Default")
      (node (ref "Q8") (pin "2") (pinfunction "B_2") (pintype "passive"))
      (node (ref "Q8") (pin "5") (pinfunction "B_5") (pintype "passive"))
      (node (ref "Q8") (pin "6") (pinfunction "C_6") (pintype "passive"))
      (node (ref "R29") (pin "1") (pinfunction "1_1") (pintype "passive"))
    )
    (net (code "53") (name "Net-(R33-Pad1)") (class "Default")
      (node (ref "R33") (pin "1") (pinfunction "1_1") (pintype "passive"))
      (node (ref "R6") (pin "2") (pinfunction "2_2") (pintype "passive"))
    )
    (net (code "54") (name "Net-(R34-Pad2)") (class "Default")
      (node (ref "R34") (pin "2") (pinfunction "2_2") (pintype "passive"))
      (node (ref "R45") (pin "1") (pinfunction "1_1") (pintype "passive"))
    )
    (net (code "55") (name "Net-(U1-EXTCLK)") (class "Default")
      (node (ref "R37") (pin "2") (pinfunction "2_2") (pintype "passive"))
      (node (ref "R38") (pin "1") (pinfunction "1_1") (pintype "passive"))
      (node (ref "U1") (pin "25") (pinfunction "EXTCLK_25") (pintype "bidirectional"))
    )
    (net (code "56") (name "Net-(U3-EN)") (class "Default")
      (node (ref "R32") (pin "2") (pinfunction "2_2") (pintype "passive"))
      (node (ref "U3") (pin "3") (pinfunction "EN_3") (pintype "bidirectional"))
    )
    (net (code "57") (name "Net-(U3-FB)") (class "Default")
      (node (ref "C4") (pin "1") (pinfunction "1_1") (pintype "passive"))
      (node (ref "R26") (pin "2") (pinfunction "2_2") (pintype "passive"))
      (node (ref "R33") (pin "2") (pinfunction "2_2") (pintype "passive"))
      (node (ref "U3") (pin "5") (pinfunction "FB_5") (pintype "bidirectional"))
    )
    (net (code "58") (name "Net-(U3-SW)") (class "Default")
      (node (ref "C7") (pin "2") (pinfunction "2_2") (pintype "passive"))
      (node (ref "L3") (pin "2") (pinfunction "2_2") (pintype "passive"))
      (node (ref "U3") (pin "6") (pinfunction "SW_6") (pintype "bidirectional"))
    )
    (net (code "59") (name "Net-(U6-EN)") (class "Default")
      (node (ref "R90") (pin "1") (pinfunction "1_1") (pintype "passive"))
      (node (ref "U6") (pin "5") (pinfunction "EN_5") (pintype "bidirectional"))
    )
    (net (code "60") (name "Net-(U6-FB)") (class "Default")
      (node (ref "R34") (pin "1") (pinfunction "1_1") (pintype "passive"))
      (node (ref "R49") (pin "2") (pinfunction "2_2") (pintype "passive"))
      (node (ref "U6") (pin "4") (pinfunction "FB_4") (pintype "bidirectional"))
    )
    (net (code "61") (name "Net-(U6-SW)") (class "Default")
      (node (ref "L1") (pin "1") (pinfunction "1_1") (pintype "passive"))
      (node (ref "U6") (pin "2") (pinfunction "SW_2") (pintype "bidirectional"))
    )
    (net (code "62") (name "Net-(X1-ENABLE)") (class "Default")
      (node (ref "R39") (pin "1") (pinfunction "1_1") (pintype "passive"))
      (node (ref "R40") (pin "1") (pinfunction "1_1") (pintype "passive"))
      (node (ref "X1") (pin "1") (pinfunction "ENABLE_1") (pintype "bidirectional"))
    )
    (net (code "63") (name "SCL") (class "Default")
      (node (ref "GND1") (pin "T") (pinfunction "T_T") (pintype "bidirectional"))
      (node (ref "J1") (pin "1") (pinfunction "1_1") (pintype "bidirectional"))
      (node (ref "Q5") (pin "2") (pinfunction "S_2") (pintype "passive"))
      (node (ref "R14") (pin "2") (pinfunction "2_2") (pintype "passive"))
    )
    (net (code "64") (name "SCL_5V") (class "Default")
      (node (ref "Q5") (pin "3") (pinfunction "D_3") (pintype "passive"))
      (node (ref "R25") (pin "2") (pinfunction "2_2") (pintype "passive"))
      (node (ref "U1") (pin "26") (pinfunction "SCL_26") (pintype "bidirectional"))
    )
    (net (code "65") (name "SDA") (class "Default")
      (node (ref "J1") (pin "2") (pinfunction "2_2") (pintype "bidirectional"))
      (node (ref "Q4") (pin "2") (pinfunction "S_2") (pintype "passive"))
      (node (ref "R13") (pin "2") (pinfunction "2_2") (pintype "passive"))
      (node (ref "VCC2") (pin "T") (pinfunction "T_T") (pintype "bidirectional"))
    )
    (net (code "66") (name "SDA_5V") (class "Default")
      (node (ref "Q4") (pin "3") (pinfunction "D_3") (pintype "passive"))
      (node (ref "R24") (pin "2") (pinfunction "2_2") (pintype "passive"))
      (node (ref "U1") (pin "27") (pinfunction "SDA_27") (pintype "bidirectional"))
    )
    (net (code "67") (name "VCC") (class "Default")
      (node (ref "C103") (pin "2") (pinfunction "2_2") (pintype "passive"))
      (node (ref "C105") (pin "2") (pinfunction "2_2") (pintype "passive"))
      (node (ref "D1") (pin "+") (pinfunction "+_+") (pintype "passive"))
      (node (ref "J1") (pin "3") (pinfunction "3_3") (pintype "bidirectional"))
      (node (ref "Q4") (pin "1") (pinfunction "G_1") (pintype "passive"))
      (node (ref "Q5") (pin "1") (pinfunction "G_1") (pintype "passive"))
      (node (ref "R13") (pin "1") (pinfunction "1_1") (pintype "passive"))
      (node (ref "R14") (pin "1") (pinfunction "1_1") (pintype "passive"))
      (node (ref "R90") (pin "2") (pinfunction "2_2") (pintype "passive"))
      (node (ref "SDA1") (pin "T") (pinfunction "T_T") (pintype "bidirectional"))
      (node (ref "U6") (pin "7") (pinfunction "AVIN_7") (pintype "bidirectional"))
      (node (ref "U6") (pin "8") (pinfunction "PVIN_8") (pintype "bidirectional"))
    )
    (net (code "68") (name "VCC_3V") (class "Default")
      (node (ref "C102") (pin "2") (pinfunction "2_2") (pintype "passive"))
      (node (ref "C104") (pin "2") (pinfunction "2_2") (pintype "passive"))
      (node (ref "C12") (pin "2") (pinfunction "2_2") (pintype "passive"))
      (node (ref "C9") (pin "2") (pinfunction "2_2") (pintype "passive"))
      (node (ref "L1") (pin "2") (pinfunction "2_2") (pintype "passive"))
      (node (ref "L3") (pin "1") (pinfunction "1_1") (pintype "passive"))
      (node (ref "R32") (pin "1") (pinfunction "1_1") (pintype "passive"))
      (node (ref "R45") (pin "2") (pinfunction "2_2") (pintype "passive"))
      (node (ref "TP12") (pin "T") (pinfunction "T_T") (pintype "bidirectional"))
      (node (ref "U3") (pin "4") (pinfunction "IN_4") (pintype "bidirectional"))
    )
    (net (code "69") (name "VCC_5V") (class "Default")
      (node (ref "C1") (pin "2") (pinfunction "2_2") (pintype "passive"))
      (node (ref "C11") (pin "2") (pinfunction "2_2") (pintype "passive"))
      (node (ref "C3") (pin "+") (pinfunction "+_+") (pintype "passive"))
      (node (ref "C4") (pin "2") (pinfunction "2_2") (pintype "passive"))
      (node (ref "C6") (pin "2") (pinfunction "2_2") (pintype "passive"))
      (node (ref "C7") (pin "1") (pinfunction "1_1") (pintype "passive"))
      (node (ref "C8") (pin "2") (pinfunction "2_2") (pintype "passive"))
      (node (ref "R1") (pin "1") (pinfunction "1_1") (pintype "passive"))
      (node (ref "R2") (pin "1") (pinfunction "1_1") (pintype "passive"))
      (node (ref "R24") (pin "1") (pinfunction "1_1") (pintype "passive"))
      (node (ref "R25") (pin "1") (pinfunction "1_1") (pintype "passive"))
      (node (ref "R3") (pin "1") (pinfunction "1_1") (pintype "passive"))
      (node (ref "R39") (pin "2") (pinfunction "2_2") (pintype "passive"))
      (node (ref "R4") (pin "1") (pinfunction "1_1") (pintype "passive"))
      (node (ref "R5") (pin "1") (pinfunction "1_1") (pintype "passive"))
      (node (ref "R6") (pin "1") (pinfunction "1_1") (pintype "passive"))
      (node (ref "R9") (pin "1") (pinfunction "1_1") (pintype "passive"))
      (node (ref "TP1") (pin "T") (pinfunction "T_T") (pintype "bidirectional"))
      (node (ref "U1") (pin "28") (pinfunction "VDD_28") (pintype "bidirectional"))
      (node (ref "U3") (pin "1") (pinfunction "OUT_1") (pintype "bidirectional"))
      (node (ref "X1") (pin "4") (pinfunction "VDD_4") (pintype "bidirectional"))
    )
  )
)
